# WSN_Gateway_v3.net
KiCad netlist of a schematic drawn in EAGLE
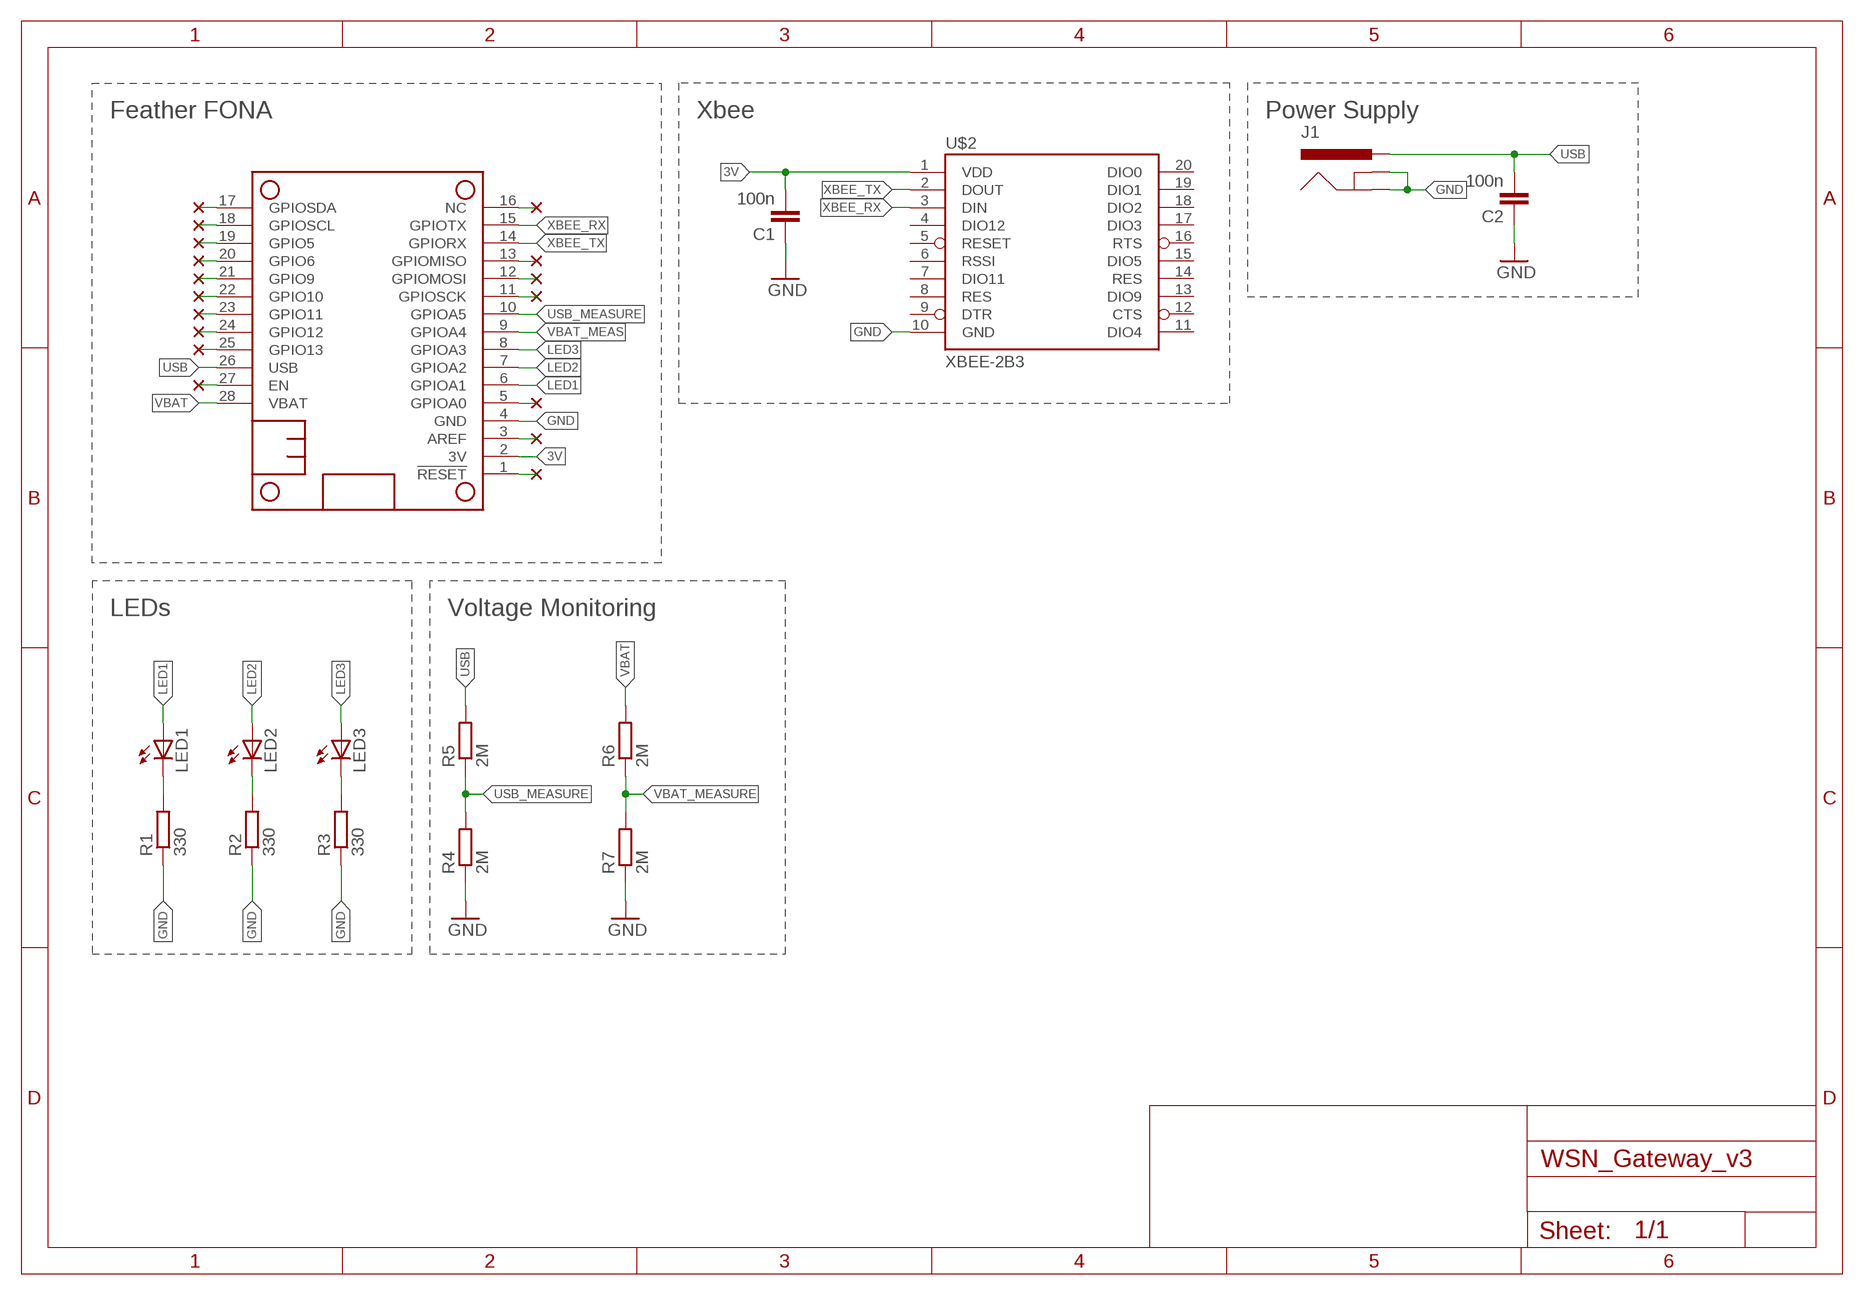
[diagram p0: schematic, sheet 1]

(export (version "E")
  (design (tool "Eeschema 10.0.6"))
  (components
    (comp (ref "C1")
      (value "100n")
      (footprint "eagle-import:C0805")
      (libsource (lib "eagle-import") (part "C"))
    )
    (comp (ref "C2")
      (value "100n")
      (footprint "eagle-import:C0805")
      (libsource (lib "eagle-import") (part "C"))
    )
    (comp (ref "J1")
      (value "5.5x2.1mm Barrel")
      (footprint "eagle-import:POWER_JACK_SMD")
      (libsource (lib "eagle-import") (part "POWER_JACKSMD"))
    )
    (comp (ref "LED1")
      (value "LEDCHIPLED_0805")
      (footprint "eagle-import:CHIPLED_0805")
      (libsource (lib "eagle-import") (part "LEDCHIPLED_0805"))
    )
    (comp (ref "LED2")
      (value "LEDCHIPLED_0805")
      (footprint "eagle-import:CHIPLED_0805")
      (libsource (lib "eagle-import") (part "LEDCHIPLED_0805"))
    )
    (comp (ref "LED3")
      (value "LEDCHIPLED_0805")
      (footprint "eagle-import:CHIPLED_0805")
      (libsource (lib "eagle-import") (part "LEDCHIPLED_0805"))
    )
    (comp (ref "MS1")
      (value "FEATHERWING_NODIM_NOHOLES")
      (footprint "eagle-import:FEATHERWING_DIM_2")
      (libsource (lib "eagle-import") (part "FEATHERWING_NODIM_NOHOLES"))
    )
    (comp (ref "R1")
      (value "330")
      (footprint "eagle-import:R0805")
      (libsource (lib "eagle-import") (part "R-EU_R0805"))
    )
    (comp (ref "R2")
      (value "330")
      (footprint "eagle-import:R0805")
      (libsource (lib "eagle-import") (part "R-EU_R0805"))
    )
    (comp (ref "R3")
      (value "330")
      (footprint "eagle-import:R0805")
      (libsource (lib "eagle-import") (part "R-EU_R0805"))
    )
    (comp (ref "R4")
      (value "2M")
      (footprint "eagle-import:R0805")
      (libsource (lib "eagle-import") (part "R-EU_R0805"))
    )
    (comp (ref "R5")
      (value "2M")
      (footprint "eagle-import:R0805")
      (libsource (lib "eagle-import") (part "R-EU_R0805"))
    )
    (comp (ref "R6")
      (value "2M")
      (footprint "eagle-import:R0805")
      (libsource (lib "eagle-import") (part "R-EU_R0805"))
    )
    (comp (ref "R7")
      (value "2M")
      (footprint "eagle-import:R0805")
      (libsource (lib "eagle-import") (part "R-EU_R0805"))
    )
    (comp (ref "U$2")
      (value "XBEE-2B3")
      (footprint "eagle-import:XBEE-SMD")
      (libsource (lib "eagle-import") (part "XBEE-2B3"))
    )
  )
  (nets
    (net (code "1") (name "3V") (class "Default")
      (node (ref "C1") (pin "2") (pinfunction "2_2") (pintype "passive"))
      (node (ref "MS1") (pin "2") (pinfunction "3V_2") (pintype "power_in"))
      (node (ref "U$2") (pin "1") (pinfunction "VDD_1") (pintype "power_in"))
    )
    (net (code "2") (name "GND") (class "Default")
      (node (ref "C1") (pin "1") (pinfunction "1_1") (pintype "passive"))
      (node (ref "C2") (pin "1") (pinfunction "1_1") (pintype "passive"))
      (node (ref "J1") (pin "GND") (pinfunction "GNDBREAK_GND") (pintype "bidirectional"))
      (node (ref "J1") (pin "P$4") (pinfunction "GND_P$4") (pintype "bidirectional"))
      (node (ref "MS1") (pin "4") (pinfunction "GND_4") (pintype "power_in"))
      (node (ref "R1") (pin "1") (pinfunction "1_1") (pintype "passive"))
      (node (ref "R2") (pin "1") (pinfunction "1_1") (pintype "passive"))
      (node (ref "R3") (pin "1") (pinfunction "1_1") (pintype "passive"))
      (node (ref "R4") (pin "1") (pinfunction "1_1") (pintype "passive"))
      (node (ref "R7") (pin "1") (pinfunction "1_1") (pintype "passive"))
      (node (ref "U$2") (pin "10") (pinfunction "GND_10") (pintype "power_in"))
    )
    (net (code "3") (name "LED1") (class "Default")
      (node (ref "LED1") (pin "A") (pinfunction "A_A") (pintype "passive"))
      (node (ref "MS1") (pin "6") (pinfunction "GPIOA1_6") (pintype "bidirectional"))
    )
    (net (code "4") (name "LED2") (class "Default")
      (node (ref "LED2") (pin "A") (pinfunction "A_A") (pintype "passive"))
      (node (ref "MS1") (pin "7") (pinfunction "GPIOA2_7") (pintype "bidirectional"))
    )
    (net (code "5") (name "LED3") (class "Default")
      (node (ref "LED3") (pin "A") (pinfunction "A_A") (pintype "passive"))
      (node (ref "MS1") (pin "8") (pinfunction "GPIOA3_8") (pintype "bidirectional"))
    )
    (net (code "6") (name "Net-(LED1-PadC)") (class "Default")
      (node (ref "LED1") (pin "C") (pinfunction "C_C") (pintype "passive"))
      (node (ref "R1") (pin "2") (pinfunction "2_2") (pintype "passive"))
    )
    (net (code "7") (name "Net-(LED2-PadC)") (class "Default")
      (node (ref "LED2") (pin "C") (pinfunction "C_C") (pintype "passive"))
      (node (ref "R2") (pin "2") (pinfunction "2_2") (pintype "passive"))
    )
    (net (code "8") (name "Net-(LED3-PadC)") (class "Default")
      (node (ref "LED3") (pin "C") (pinfunction "C_C") (pintype "passive"))
      (node (ref "R3") (pin "2") (pinfunction "2_2") (pintype "passive"))
    )
    (net (code "9") (name "USB") (class "Default")
      (node (ref "C2") (pin "2") (pinfunction "2_2") (pintype "passive"))
      (node (ref "J1") (pin "VIN0") (pinfunction "PWR_VIN0") (pintype "bidirectional"))
      (node (ref "J1") (pin "VIN1") (pinfunction "PWR_VIN1") (pintype "bidirectional"))
      (node (ref "MS1") (pin "26") (pinfunction "USB_26") (pintype "power_in"))
      (node (ref "R5") (pin "2") (pinfunction "2_2") (pintype "passive"))
    )
    (net (code "10") (name "USB_MEASURE") (class "Default")
      (node (ref "MS1") (pin "10") (pinfunction "GPIOA5_10") (pintype "bidirectional"))
      (node (ref "R4") (pin "2") (pinfunction "2_2") (pintype "passive"))
      (node (ref "R5") (pin "1") (pinfunction "1_1") (pintype "passive"))
    )
    (net (code "11") (name "VBAT") (class "Default")
      (node (ref "MS1") (pin "28") (pinfunction "VBAT_28") (pintype "power_in"))
      (node (ref "R6") (pin "2") (pinfunction "2_2") (pintype "passive"))
    )
    (net (code "12") (name "VBAT_MEAS") (class "Default")
      (node (ref "MS1") (pin "9") (pinfunction "GPIOA4_9") (pintype "bidirectional"))
    )
    (net (code "13") (name "VBAT_MEASURE") (class "Default")
      (node (ref "R6") (pin "1") (pinfunction "1_1") (pintype "passive"))
      (node (ref "R7") (pin "2") (pinfunction "2_2") (pintype "passive"))
    )
    (net (code "14") (name "XBEE_RX") (class "Default")
      (node (ref "MS1") (pin "15") (pinfunction "GPIOTX_15") (pintype "bidirectional"))
      (node (ref "U$2") (pin "3") (pinfunction "DIN_3") (pintype "input"))
    )
    (net (code "15") (name "XBEE_TX") (class "Default")
      (node (ref "MS1") (pin "14") (pinfunction "GPIORX_14") (pintype "bidirectional"))
      (node (ref "U$2") (pin "2") (pinfunction "DOUT_2") (pintype "output"))
    )
    (net (code "16") (name "unconnected-(MS1-AREF-Pad3)") (class "Default")
      (node (ref "MS1") (pin "3") (pinfunction "AREF_3") (pintype "passive"))
    )
    (net (code "17") (name "unconnected-(MS1-EN-Pad27)") (class "Default")
      (node (ref "MS1") (pin "27") (pinfunction "EN_27") (pintype "passive"))
    )
    (net (code "18") (name "unconnected-(MS1-GPIO5-Pad19)") (class "Default")
      (node (ref "MS1") (pin "19") (pinfunction "GPIO5_19") (pintype "bidirectional"))
    )
    (net (code "19") (name "unconnected-(MS1-GPIO6-Pad20)") (class "Default")
      (node (ref "MS1") (pin "20") (pinfunction "GPIO6_20") (pintype "bidirectional"))
    )
    (net (code "20") (name "unconnected-(MS1-GPIO9-Pad21)") (class "Default")
      (node (ref "MS1") (pin "21") (pinfunction "GPIO9_21") (pintype "bidirectional"))
    )
    (net (code "21") (name "unconnected-(MS1-GPIO10-Pad22)") (class "Default")
      (node (ref "MS1") (pin "22") (pinfunction "GPIO10_22") (pintype "bidirectional"))
    )
    (net (code "22") (name "unconnected-(MS1-GPIO11-Pad23)") (class "Default")
      (node (ref "MS1") (pin "23") (pinfunction "GPIO11_23") (pintype "bidirectional"))
    )
    (net (code "23") (name "unconnected-(MS1-GPIO12-Pad24)") (class "Default")
      (node (ref "MS1") (pin "24") (pinfunction "GPIO12_24") (pintype "bidirectional"))
    )
    (net (code "24") (name "unconnected-(MS1-GPIO13-Pad25)") (class "Default")
      (node (ref "MS1") (pin "25") (pinfunction "GPIO13_25") (pintype "bidirectional"))
    )
    (net (code "25") (name "unconnected-(MS1-GPIOA0-Pad5)") (class "Default")
      (node (ref "MS1") (pin "5") (pinfunction "GPIOA0_5") (pintype "bidirectional"))
    )
    (net (code "26") (name "unconnected-(MS1-GPIOMISO-Pad13)") (class "Default")
      (node (ref "MS1") (pin "13") (pinfunction "GPIOMISO_13") (pintype "bidirectional"))
    )
    (net (code "27") (name "unconnected-(MS1-GPIOMOSI-Pad12)") (class "Default")
      (node (ref "MS1") (pin "12") (pinfunction "GPIOMOSI_12") (pintype "bidirectional"))
    )
    (net (code "28") (name "unconnected-(MS1-GPIOSCK-Pad11)") (class "Default")
      (node (ref "MS1") (pin "11") (pinfunction "GPIOSCK_11") (pintype "bidirectional"))
    )
    (net (code "29") (name "unconnected-(MS1-GPIOSCL-Pad18)") (class "Default")
      (node (ref "MS1") (pin "18") (pinfunction "GPIOSCL_18") (pintype "bidirectional"))
    )
    (net (code "30") (name "unconnected-(MS1-GPIOSDA-Pad17)") (class "Default")
      (node (ref "MS1") (pin "17") (pinfunction "GPIOSDA_17") (pintype "bidirectional"))
    )
    (net (code "31") (name "unconnected-(MS1-NC-Pad16)") (class "Default")
      (node (ref "MS1") (pin "16") (pinfunction "NC_16") (pintype "passive"))
    )
    (net (code "32") (name "unconnected-(MS1-~{RESET}-Pad1)") (class "Default")
      (node (ref "MS1") (pin "1") (pinfunction "~{RESET}_1") (pintype "input"))
    )
    (net (code "33") (name "unconnected-(U$2-CTS-Pad12)") (class "Default")
      (node (ref "U$2") (pin "12") (pinfunction "CTS_12") (pintype "output"))
    )
    (net (code "34") (name "unconnected-(U$2-DIO0-Pad20)") (class "Default")
      (node (ref "U$2") (pin "20") (pinfunction "DIO0_20") (pintype "bidirectional"))
    )
    (net (code "35") (name "unconnected-(U$2-DIO1-Pad19)") (class "Default")
      (node (ref "U$2") (pin "19") (pinfunction "DIO1_19") (pintype "bidirectional"))
    )
    (net (code "36") (name "unconnected-(U$2-DIO2-Pad18)") (class "Default")
      (node (ref "U$2") (pin "18") (pinfunction "DIO2_18") (pintype "bidirectional"))
    )
    (net (code "37") (name "unconnected-(U$2-DIO3-Pad17)") (class "Default")
      (node (ref "U$2") (pin "17") (pinfunction "DIO3_17") (pintype "bidirectional"))
    )
    (net (code "38") (name "unconnected-(U$2-DIO4-Pad11)") (class "Default")
      (node (ref "U$2") (pin "11") (pinfunction "DIO4_11") (pintype "bidirectional"))
    )
    (net (code "39") (name "unconnected-(U$2-DIO5-Pad15)") (class "Default")
      (node (ref "U$2") (pin "15") (pinfunction "DIO5_15") (pintype "bidirectional"))
    )
    (net (code "40") (name "unconnected-(U$2-DIO9-Pad13)") (class "Default")
      (node (ref "U$2") (pin "13") (pinfunction "DIO9_13") (pintype "bidirectional"))
    )
    (net (code "41") (name "unconnected-(U$2-DIO11-Pad7)") (class "Default")
      (node (ref "U$2") (pin "7") (pinfunction "DIO11_7") (pintype "bidirectional"))
    )
    (net (code "42") (name "unconnected-(U$2-DIO12-Pad4)") (class "Default")
      (node (ref "U$2") (pin "4") (pinfunction "DIO12_4") (pintype "bidirectional"))
    )
    (net (code "43") (name "unconnected-(U$2-DTR-Pad9)") (class "Default")
      (node (ref "U$2") (pin "9") (pinfunction "DTR_9") (pintype "bidirectional"))
    )
    (net (code "44") (name "unconnected-(U$2-RES-Pad8)") (class "Default")
      (node (ref "U$2") (pin "8") (pinfunction "RES_8") (pintype "bidirectional"))
    )
    (net (code "45") (name "unconnected-(U$2-RES-Pad14)") (class "Default")
      (node (ref "U$2") (pin "14") (pinfunction "RES_14") (pintype "bidirectional"))
    )
    (net (code "46") (name "unconnected-(U$2-RESET-Pad5)") (class "Default")
      (node (ref "U$2") (pin "5") (pinfunction "RESET_5") (pintype "input"))
    )
    (net (code "47") (name "unconnected-(U$2-RSSI-Pad6)") (class "Default")
      (node (ref "U$2") (pin "6") (pinfunction "RSSI_6") (pintype "bidirectional"))
    )
    (net (code "48") (name "unconnected-(U$2-RTS-Pad16)") (class "Default")
      (node (ref "U$2") (pin "16") (pinfunction "RTS_16") (pintype "input"))
    )
  )
)
